# PCA9622DR.net
KiCad netlist of a schematic drawn in EAGLE
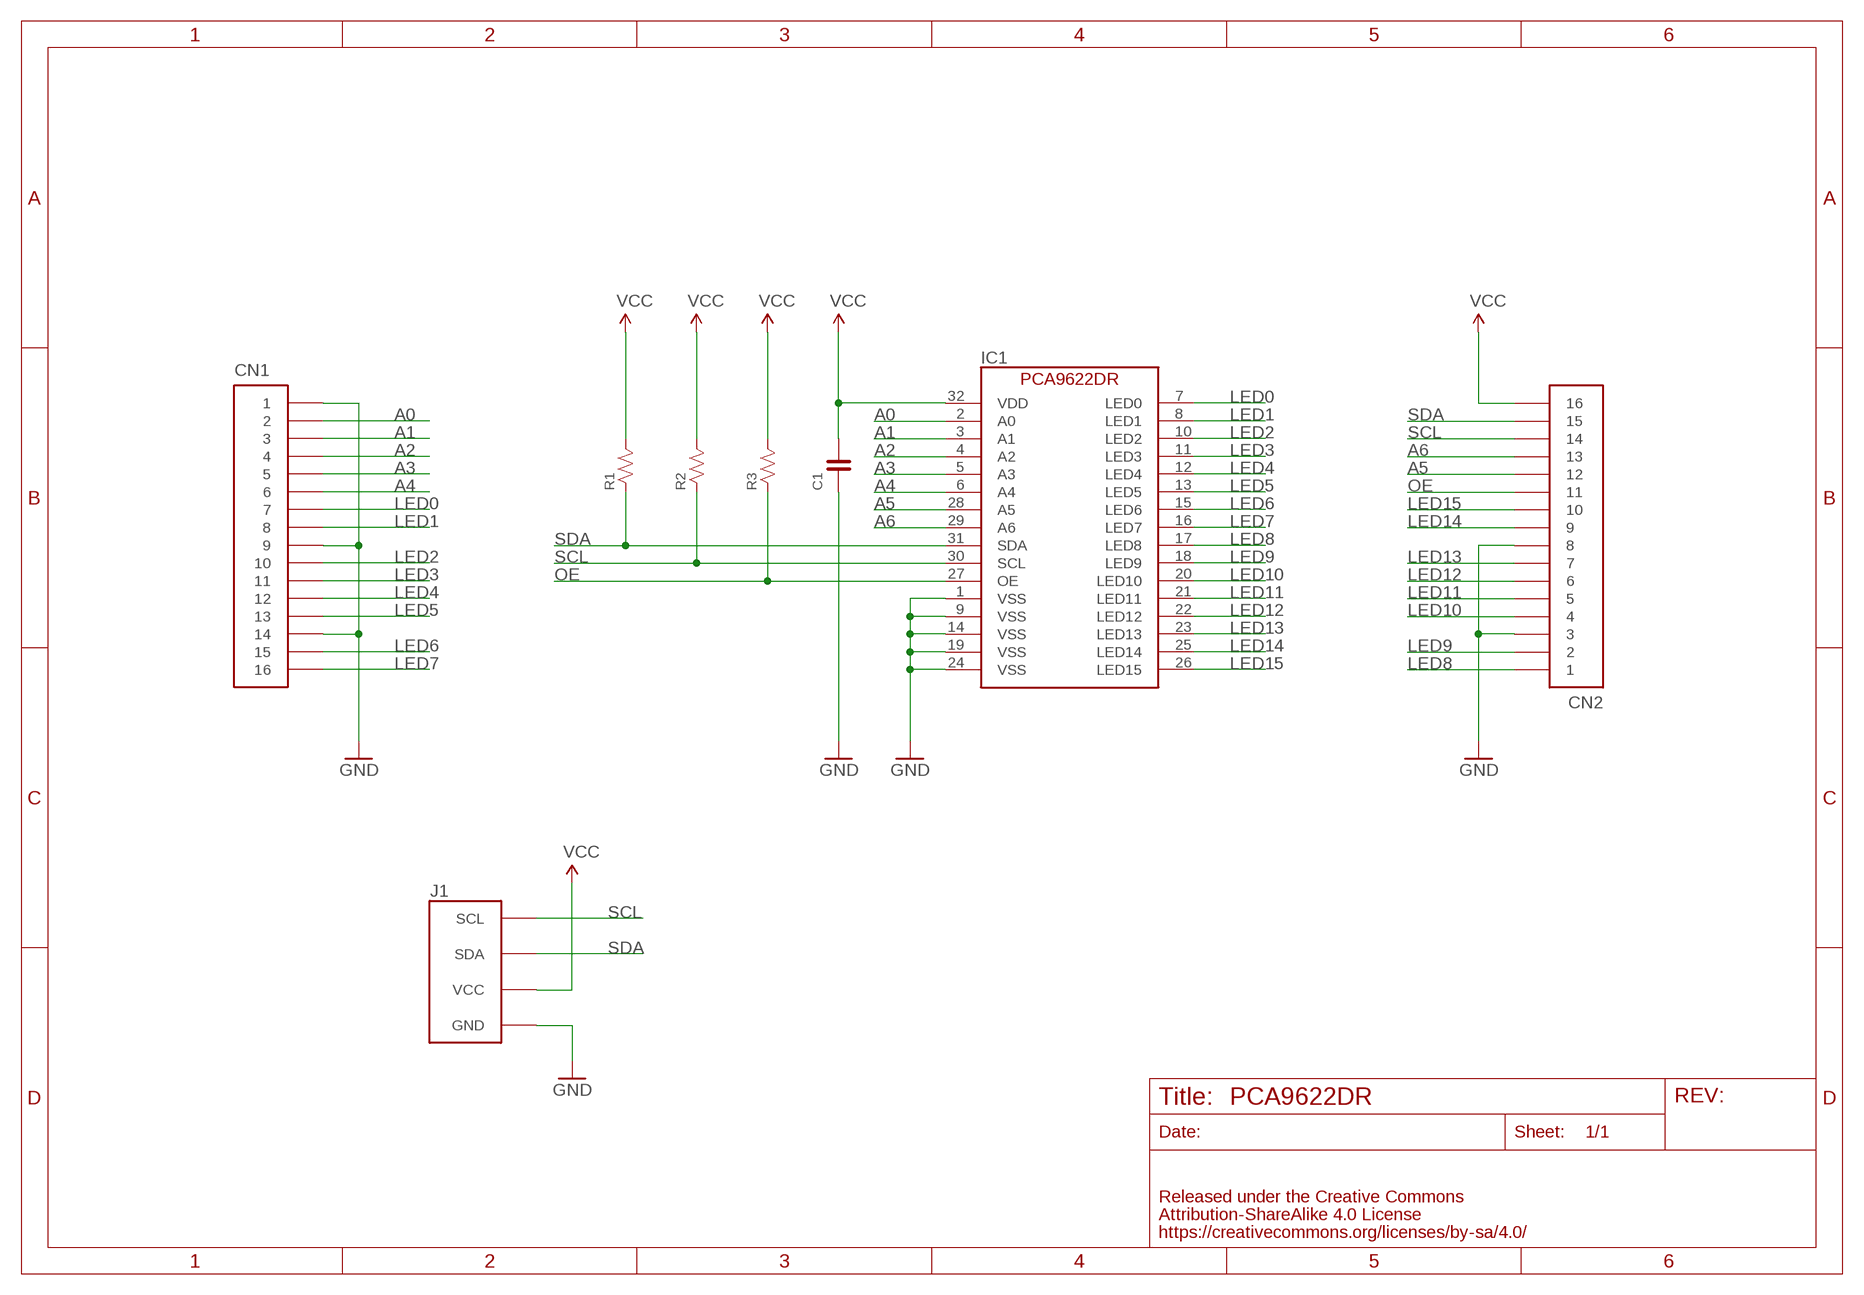
[diagram p0: schematic, sheet 1]

(export (version "E")
  (design (tool "Eeschema 10.0.6"))
  (components
    (comp (ref "C1")
      (value "CAPACITOR-0603")
      (footprint "eagle-import:0603")
      (libsource (lib "eagle-import") (part "CAPACITOR-0603"))
    )
    (comp (ref "CN1")
      (value "PIN_HEADER_1X16")
      (footprint "eagle-import:PIN_1X16_SNEAKY")
      (libsource (lib "eagle-import") (part "PIN_HEADER_1X16"))
    )
    (comp (ref "CN2")
      (value "PIN_HEADER_1X16")
      (footprint "eagle-import:PIN_1X16_SNEAKY")
      (libsource (lib "eagle-import") (part "PIN_HEADER_1X16"))
    )
    (comp (ref "IC1")
      (value "PCA9622DR")
      (footprint "eagle-import:TSSOP32")
      (libsource (lib "eagle-import") (part "PCA9622DR"))
    )
    (comp (ref "J1")
      (value "FABO_BRICK_I2C-CONNECTOR")
      (footprint "eagle-import:FABO_BRICK_I2C_CONNECTOR")
      (libsource (lib "eagle-import") (part "FABO_BRICK_I2C-CONNECTOR"))
    )
    (comp (ref "R1")
      (value "RESISTOR-0603")
      (footprint "eagle-import:0603")
      (libsource (lib "eagle-import") (part "RESISTOR-0603"))
    )
    (comp (ref "R2")
      (value "RESISTOR-0603")
      (footprint "eagle-import:0603")
      (libsource (lib "eagle-import") (part "RESISTOR-0603"))
    )
    (comp (ref "R3")
      (value "RESISTOR-0603")
      (footprint "eagle-import:0603")
      (libsource (lib "eagle-import") (part "RESISTOR-0603"))
    )
  )
  (nets
    (net (code "1") (name "/A0") (class "Default")
      (node (ref "CN1") (pin "2") (pinfunction "2_2") (pintype "bidirectional"))
      (node (ref "IC1") (pin "2") (pinfunction "A0_2") (pintype "bidirectional"))
    )
    (net (code "2") (name "/A1") (class "Default")
      (node (ref "CN1") (pin "3") (pinfunction "3_3") (pintype "bidirectional"))
      (node (ref "IC1") (pin "3") (pinfunction "A1_3") (pintype "bidirectional"))
    )
    (net (code "3") (name "/A2") (class "Default")
      (node (ref "CN1") (pin "4") (pinfunction "4_4") (pintype "bidirectional"))
      (node (ref "IC1") (pin "4") (pinfunction "A2_4") (pintype "bidirectional"))
    )
    (net (code "4") (name "/A3") (class "Default")
      (node (ref "CN1") (pin "5") (pinfunction "5_5") (pintype "bidirectional"))
      (node (ref "IC1") (pin "5") (pinfunction "A3_5") (pintype "bidirectional"))
    )
    (net (code "5") (name "/A4") (class "Default")
      (node (ref "CN1") (pin "6") (pinfunction "6_6") (pintype "bidirectional"))
      (node (ref "IC1") (pin "6") (pinfunction "A4_6") (pintype "bidirectional"))
    )
    (net (code "6") (name "/A5") (class "Default")
      (node (ref "CN2") (pin "12") (pinfunction "12_12") (pintype "bidirectional"))
      (node (ref "IC1") (pin "28") (pinfunction "A5_28") (pintype "bidirectional"))
    )
    (net (code "7") (name "/A6") (class "Default")
      (node (ref "CN2") (pin "13") (pinfunction "13_13") (pintype "bidirectional"))
      (node (ref "IC1") (pin "29") (pinfunction "A6_29") (pintype "bidirectional"))
    )
    (net (code "8") (name "/LED0") (class "Default")
      (node (ref "CN1") (pin "7") (pinfunction "7_7") (pintype "bidirectional"))
      (node (ref "IC1") (pin "7") (pinfunction "LED0_7") (pintype "bidirectional"))
    )
    (net (code "9") (name "/LED1") (class "Default")
      (node (ref "CN1") (pin "8") (pinfunction "8_8") (pintype "bidirectional"))
      (node (ref "IC1") (pin "8") (pinfunction "LED1_8") (pintype "bidirectional"))
    )
    (net (code "10") (name "/LED2") (class "Default")
      (node (ref "CN1") (pin "10") (pinfunction "10_10") (pintype "bidirectional"))
      (node (ref "IC1") (pin "10") (pinfunction "LED2_10") (pintype "bidirectional"))
    )
    (net (code "11") (name "/LED3") (class "Default")
      (node (ref "CN1") (pin "11") (pinfunction "11_11") (pintype "bidirectional"))
      (node (ref "IC1") (pin "11") (pinfunction "LED3_11") (pintype "bidirectional"))
    )
    (net (code "12") (name "/LED4") (class "Default")
      (node (ref "CN1") (pin "12") (pinfunction "12_12") (pintype "bidirectional"))
      (node (ref "IC1") (pin "12") (pinfunction "LED4_12") (pintype "bidirectional"))
    )
    (net (code "13") (name "/LED5") (class "Default")
      (node (ref "CN1") (pin "13") (pinfunction "13_13") (pintype "bidirectional"))
      (node (ref "IC1") (pin "13") (pinfunction "LED5_13") (pintype "bidirectional"))
    )
    (net (code "14") (name "/LED6") (class "Default")
      (node (ref "CN1") (pin "15") (pinfunction "15_15") (pintype "bidirectional"))
      (node (ref "IC1") (pin "15") (pinfunction "LED6_15") (pintype "bidirectional"))
    )
    (net (code "15") (name "/LED7") (class "Default")
      (node (ref "CN1") (pin "16") (pinfunction "16_16") (pintype "bidirectional"))
      (node (ref "IC1") (pin "16") (pinfunction "LED7_16") (pintype "bidirectional"))
    )
    (net (code "16") (name "/LED8") (class "Default")
      (node (ref "CN2") (pin "1") (pinfunction "1_1") (pintype "bidirectional"))
      (node (ref "IC1") (pin "17") (pinfunction "LED8_17") (pintype "bidirectional"))
    )
    (net (code "17") (name "/LED9") (class "Default")
      (node (ref "CN2") (pin "2") (pinfunction "2_2") (pintype "bidirectional"))
      (node (ref "IC1") (pin "18") (pinfunction "LED9_18") (pintype "bidirectional"))
    )
    (net (code "18") (name "/LED10") (class "Default")
      (node (ref "CN2") (pin "4") (pinfunction "4_4") (pintype "bidirectional"))
      (node (ref "IC1") (pin "20") (pinfunction "LED10_20") (pintype "bidirectional"))
    )
    (net (code "19") (name "/LED11") (class "Default")
      (node (ref "CN2") (pin "5") (pinfunction "5_5") (pintype "bidirectional"))
      (node (ref "IC1") (pin "21") (pinfunction "LED11_21") (pintype "bidirectional"))
    )
    (net (code "20") (name "/LED12") (class "Default")
      (node (ref "CN2") (pin "6") (pinfunction "6_6") (pintype "bidirectional"))
      (node (ref "IC1") (pin "22") (pinfunction "LED12_22") (pintype "bidirectional"))
    )
    (net (code "21") (name "/LED13") (class "Default")
      (node (ref "CN2") (pin "7") (pinfunction "7_7") (pintype "bidirectional"))
      (node (ref "IC1") (pin "23") (pinfunction "LED13_23") (pintype "bidirectional"))
    )
    (net (code "22") (name "/LED14") (class "Default")
      (node (ref "CN2") (pin "9") (pinfunction "9_9") (pintype "bidirectional"))
      (node (ref "IC1") (pin "25") (pinfunction "LED14_25") (pintype "bidirectional"))
    )
    (net (code "23") (name "/LED15") (class "Default")
      (node (ref "CN2") (pin "10") (pinfunction "10_10") (pintype "bidirectional"))
      (node (ref "IC1") (pin "26") (pinfunction "LED15_26") (pintype "bidirectional"))
    )
    (net (code "24") (name "/OE") (class "Default")
      (node (ref "CN2") (pin "11") (pinfunction "11_11") (pintype "bidirectional"))
      (node (ref "IC1") (pin "27") (pinfunction "OE_27") (pintype "bidirectional"))
      (node (ref "R3") (pin "1") (pinfunction "1_1") (pintype "bidirectional"))
    )
    (net (code "25") (name "/SCL") (class "Default")
      (node (ref "CN2") (pin "14") (pinfunction "14_14") (pintype "bidirectional"))
      (node (ref "IC1") (pin "30") (pinfunction "SCL_30") (pintype "bidirectional"))
      (node (ref "J1") (pin "SCL") (pinfunction "SCL_SCL") (pintype "bidirectional"))
      (node (ref "R2") (pin "1") (pinfunction "1_1") (pintype "bidirectional"))
    )
    (net (code "26") (name "/SDA") (class "Default")
      (node (ref "CN2") (pin "15") (pinfunction "15_15") (pintype "bidirectional"))
      (node (ref "IC1") (pin "31") (pinfunction "SDA_31") (pintype "bidirectional"))
      (node (ref "J1") (pin "SDA") (pinfunction "SDA_SDA") (pintype "bidirectional"))
      (node (ref "R1") (pin "1") (pinfunction "1_1") (pintype "bidirectional"))
    )
    (net (code "27") (name "GND") (class "Default")
      (node (ref "C1") (pin "1") (pinfunction "1_1") (pintype "passive"))
      (node (ref "CN1") (pin "1") (pinfunction "1_1") (pintype "bidirectional"))
      (node (ref "CN1") (pin "14") (pinfunction "14_14") (pintype "bidirectional"))
      (node (ref "CN1") (pin "9") (pinfunction "9_9") (pintype "bidirectional"))
      (node (ref "CN2") (pin "3") (pinfunction "3_3") (pintype "bidirectional"))
      (node (ref "CN2") (pin "8") (pinfunction "8_8") (pintype "bidirectional"))
      (node (ref "IC1") (pin "1") (pinfunction "VSS_1") (pintype "bidirectional"))
      (node (ref "IC1") (pin "14") (pinfunction "VSS_14") (pintype "bidirectional"))
      (node (ref "IC1") (pin "19") (pinfunction "VSS_19") (pintype "bidirectional"))
      (node (ref "IC1") (pin "24") (pinfunction "VSS_24") (pintype "bidirectional"))
      (node (ref "IC1") (pin "9") (pinfunction "VSS_9") (pintype "bidirectional"))
      (node (ref "J1") (pin "GND") (pinfunction "GND_GND") (pintype "bidirectional"))
    )
    (net (code "28") (name "VCC") (class "Default")
      (node (ref "C1") (pin "2") (pinfunction "2_2") (pintype "passive"))
      (node (ref "CN2") (pin "16") (pinfunction "16_16") (pintype "bidirectional"))
      (node (ref "IC1") (pin "32") (pinfunction "VDD_32") (pintype "bidirectional"))
      (node (ref "J1") (pin "VCC") (pinfunction "VCC_VCC") (pintype "bidirectional"))
      (node (ref "R1") (pin "2") (pinfunction "2_2") (pintype "bidirectional"))
      (node (ref "R2") (pin "2") (pinfunction "2_2") (pintype "bidirectional"))
      (node (ref "R3") (pin "2") (pinfunction "2_2") (pintype "bidirectional"))
    )
  )
)
